# Cansat2019_3279_Container_v02.net
KiCad netlist of a schematic drawn in EAGLE
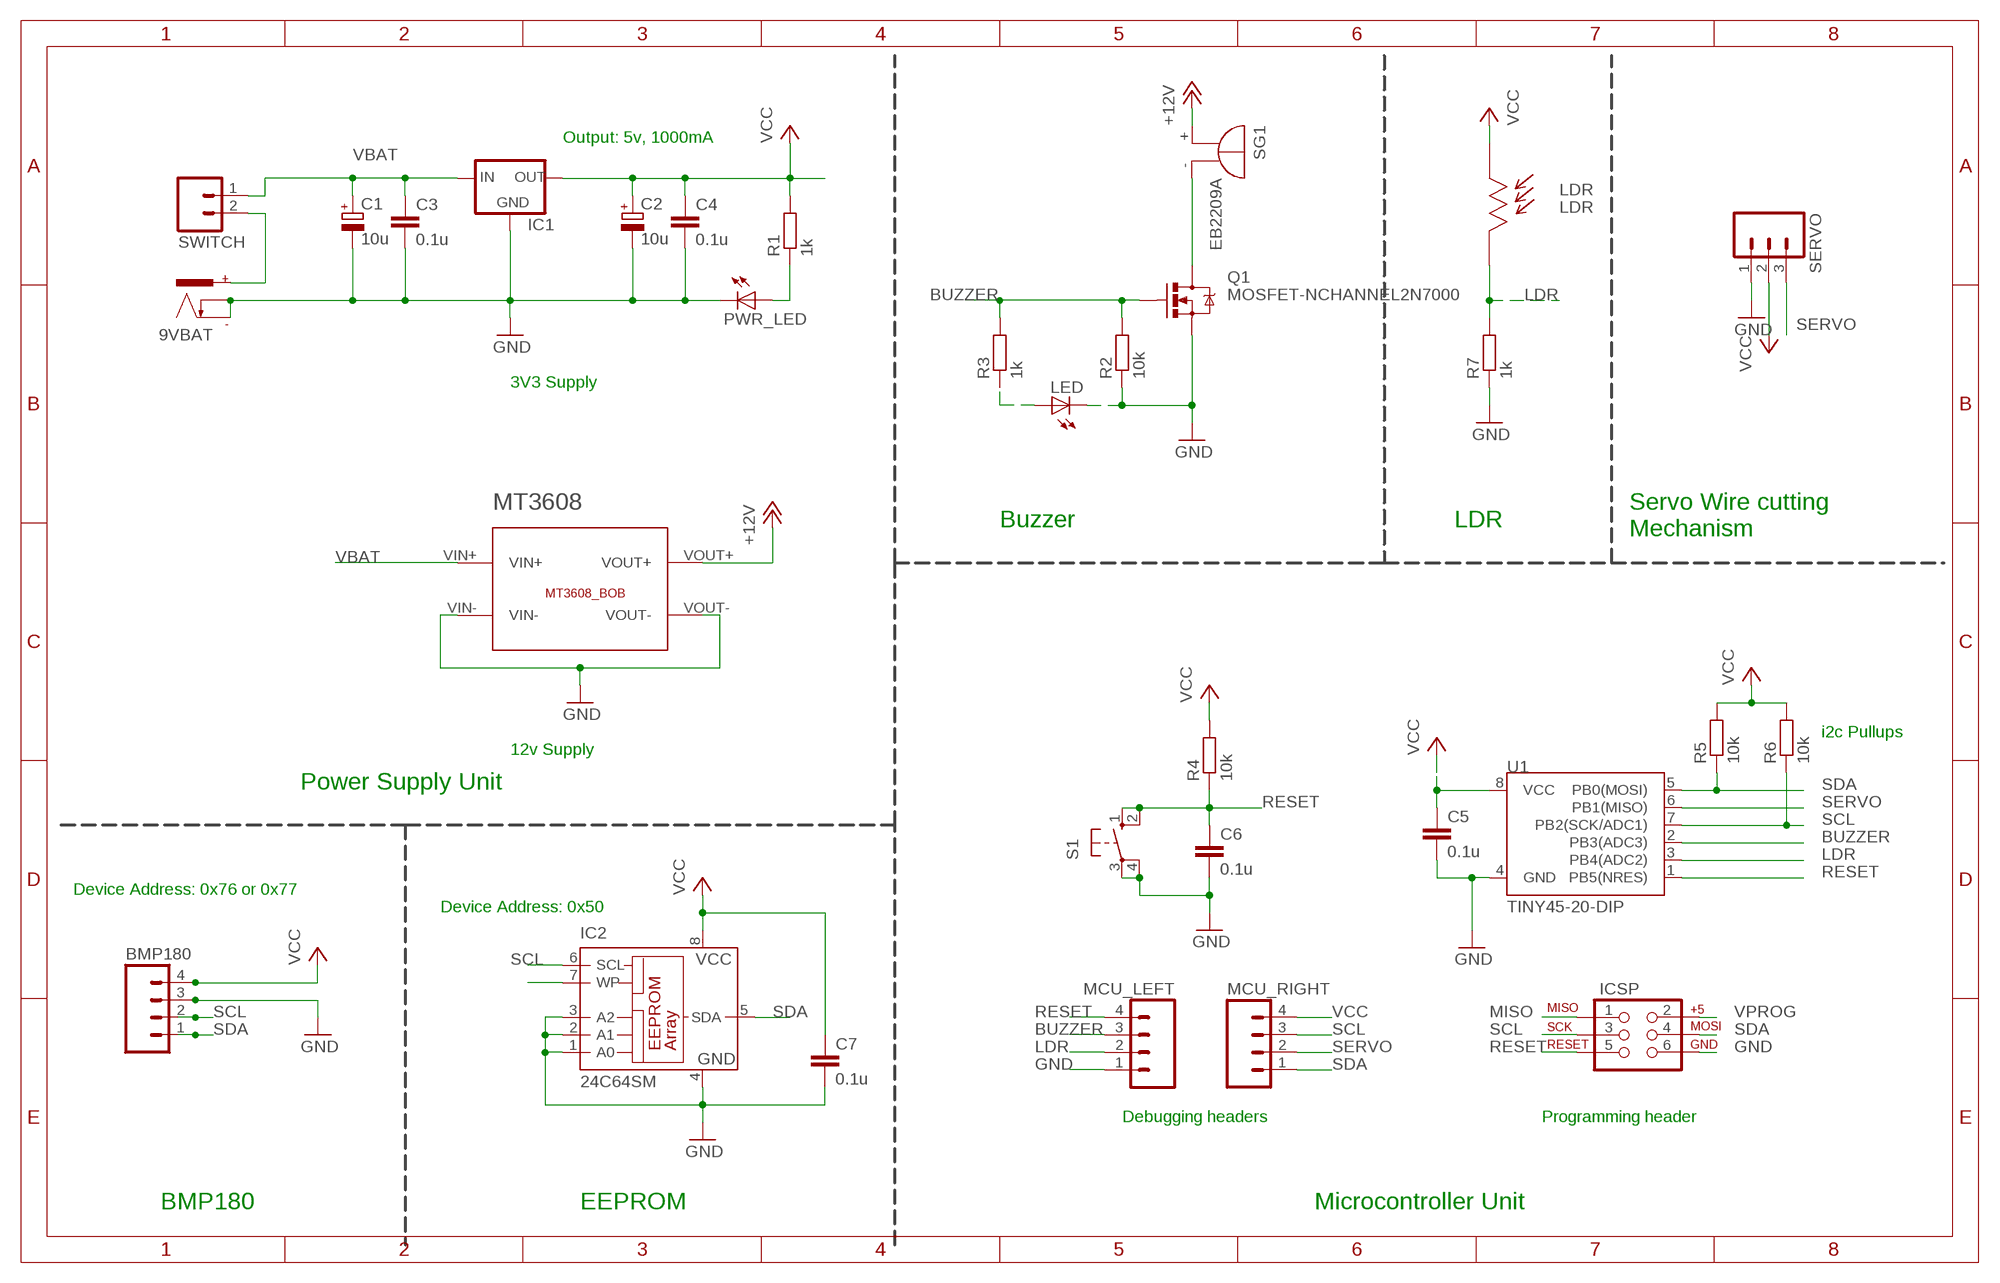
[diagram p0: schematic, sheet 1]

(export (version "E")
  (design (tool "Eeschema 10.0.6"))
  (components
    (comp (ref "9VBAT")
      (value "POWER_CON")
      (footprint "eagle-import:NEB21R")
      (libsource (lib "eagle-import") (part "POWER_CON"))
    )
    (comp (ref "BMP180")
      (value "M04")
      (footprint "eagle-import:04P")
      (libsource (lib "eagle-import") (part "M04"))
    )
    (comp (ref "C1")
      (value "10u")
      (footprint "eagle-import:E2,5-6")
      (libsource (lib "eagle-import") (part "CPOL-EUE2.5-6"))
    )
    (comp (ref "C2")
      (value "10u")
      (footprint "eagle-import:E2,5-6")
      (libsource (lib "eagle-import") (part "CPOL-EUE2.5-6"))
    )
    (comp (ref "C3")
      (value "0.1u")
      (footprint "eagle-import:C025-025X050")
      (libsource (lib "eagle-import") (part "C-EU025-025X050"))
    )
    (comp (ref "C4")
      (value "0.1u")
      (footprint "eagle-import:C025-025X050")
      (libsource (lib "eagle-import") (part "C-EU025-025X050"))
    )
    (comp (ref "C5")
      (value "0.1u")
      (footprint "eagle-import:C025-025X050")
      (libsource (lib "eagle-import") (part "C-EU025-025X050"))
    )
    (comp (ref "C6")
      (value "0.1u")
      (footprint "eagle-import:C025-025X050")
      (libsource (lib "eagle-import") (part "C-EU025-025X050"))
    )
    (comp (ref "C7")
      (value "0.1u")
      (footprint "eagle-import:C025-025X050")
      (libsource (lib "eagle-import") (part "C-EU025-025X050"))
    )
    (comp (ref "IC1")
      (value "V_REG_78XX-TO-220")
      (footprint "eagle-import:TO-220-ALT")
      (libsource (lib "eagle-import") (part "V_REG_78XX-TO-220"))
    )
    (comp (ref "IC2")
      (value "24C64SM")
      (footprint "eagle-import:SO-08M")
      (fields (field (name "MF") "RAMTRON INTERNATIONAL CORP") (field (name "MPN") "FM24C64-S"))
      (libsource (lib "eagle-import") (part "24SMC64"))
    )
    (comp (ref "ICSP")
      (value "AVR_SPI_PRG_6NS")
      (footprint "eagle-import:2X3-NS")
      (libsource (lib "eagle-import") (part "AVR_SPI_PRG_6NS"))
    )
    (comp (ref "LDR")
      (value "LDR")
      (footprint "eagle-import:LDR-5MM")
      (libsource (lib "eagle-import") (part "LDR"))
    )
    (comp (ref "LED")
      (value "LED3MM")
      (footprint "eagle-import:LED3MM")
      (libsource (lib "eagle-import") (part "LED3MM"))
    )
    (comp (ref "MCU_LEFT")
      (value "M04")
      (footprint "eagle-import:04P")
      (libsource (lib "eagle-import") (part "M04"))
    )
    (comp (ref "MCU_RIGHT")
      (value "M04")
      (footprint "eagle-import:04P")
      (libsource (lib "eagle-import") (part "M04"))
    )
    (comp (ref "MT3608")
      (value "MT3608_BOB")
      (footprint "eagle-import:MT3608_BOB")
      (libsource (lib "eagle-import") (part "MT3608_BOB"))
    )
    (comp (ref "PWR_LED")
      (value "LED3MM")
      (footprint "eagle-import:LED3MM")
      (libsource (lib "eagle-import") (part "LED3MM"))
    )
    (comp (ref "Q1")
      (value "MOSFET-NCHANNEL2N7000")
      (footprint "eagle-import:TO-92")
      (libsource (lib "eagle-import") (part "MOSFET-NCHANNEL2N7000"))
    )
    (comp (ref "R1")
      (value "1k")
      (footprint "eagle-import:0204_7")
      (libsource (lib "eagle-import") (part "R-EU_0204/7"))
    )
    (comp (ref "R2")
      (value "10k")
      (footprint "eagle-import:0204_7")
      (libsource (lib "eagle-import") (part "R-EU_0204/7"))
    )
    (comp (ref "R3")
      (value "1k")
      (footprint "eagle-import:0204_7")
      (libsource (lib "eagle-import") (part "R-EU_0204/7"))
    )
    (comp (ref "R4")
      (value "10k")
      (footprint "eagle-import:0204_7")
      (libsource (lib "eagle-import") (part "R-EU_0204/7"))
    )
    (comp (ref "R5")
      (value "10k")
      (footprint "eagle-import:0204_7")
      (libsource (lib "eagle-import") (part "R-EU_0204/7"))
    )
    (comp (ref "R6")
      (value "10k")
      (footprint "eagle-import:0204_7")
      (libsource (lib "eagle-import") (part "R-EU_0204/7"))
    )
    (comp (ref "R7")
      (value "1k")
      (footprint "eagle-import:0204_7")
      (libsource (lib "eagle-import") (part "R-EU_0204/7"))
    )
    (comp (ref "S1")
      (value "PUSH-BUTTON-6MM")
      (footprint "eagle-import:B3F-10XX")
      (libsource (lib "eagle-import") (part "PUSH-BUTTON-6MM"))
    )
    (comp (ref "SERVO")
      (value "M03")
      (footprint "eagle-import:03P")
      (libsource (lib "eagle-import") (part "M03"))
    )
    (comp (ref "SG1")
      (value "EB2209A")
      (footprint "eagle-import:EB2209A")
      (libsource (lib "eagle-import") (part "EB2209A"))
    )
    (comp (ref "SWITCH")
      (value "M02")
      (footprint "eagle-import:02P")
      (libsource (lib "eagle-import") (part "M02"))
    )
    (comp (ref "U1")
      (value "TINY45-20-DIP")
      (footprint "eagle-import:DIP08")
      (libsource (lib "eagle-import") (part "ATTINY45TINY45-20-DIP"))
    )
  )
  (nets
    (net (code "1") (name "+12V") (class "Default")
      (node (ref "MT3608") (pin "VOUT+") (pinfunction "VOUT+_VOUT+") (pintype "bidirectional"))
      (node (ref "SG1") (pin "+") (pinfunction "+_+") (pintype "passive"))
    )
    (net (code "2") (name "/BUZZER") (class "Default")
      (node (ref "MCU_LEFT") (pin "3") (pinfunction "3_3") (pintype "passive"))
      (node (ref "Q1") (pin "2") (pinfunction "G_2") (pintype "passive"))
      (node (ref "R2") (pin "2") (pinfunction "2_2") (pintype "passive"))
      (node (ref "R3") (pin "2") (pinfunction "2_2") (pintype "passive"))
      (node (ref "U1") (pin "2") (pinfunction "PB3(ADC3)_2") (pintype "bidirectional"))
    )
    (net (code "3") (name "/LDR") (class "Default")
      (node (ref "LDR") (pin "P$2") (pinfunction "P$2_P$2") (pintype "bidirectional"))
      (node (ref "MCU_LEFT") (pin "2") (pinfunction "2_2") (pintype "passive"))
      (node (ref "R7") (pin "2") (pinfunction "2_2") (pintype "passive"))
      (node (ref "U1") (pin "3") (pinfunction "PB4(ADC2)_3") (pintype "bidirectional"))
    )
    (net (code "4") (name "/MISO") (class "Default")
      (node (ref "ICSP") (pin "1") (pinfunction "1_1") (pintype "passive"))
    )
    (net (code "5") (name "/RESET") (class "Default")
      (node (ref "C6") (pin "1") (pinfunction "1_1") (pintype "passive"))
      (node (ref "ICSP") (pin "5") (pinfunction "5_5") (pintype "passive"))
      (node (ref "MCU_LEFT") (pin "4") (pinfunction "4_4") (pintype "passive"))
      (node (ref "R4") (pin "1") (pinfunction "1_1") (pintype "passive"))
      (node (ref "S1") (pin "1") (pinfunction "S_1") (pintype "passive"))
      (node (ref "S1") (pin "2") (pinfunction "S1_2") (pintype "passive"))
      (node (ref "U1") (pin "1") (pinfunction "PB5(NRES)_1") (pintype "bidirectional"))
    )
    (net (code "6") (name "/SCL") (class "Default")
      (node (ref "BMP180") (pin "2") (pinfunction "2_2") (pintype "passive"))
      (node (ref "IC2") (pin "6") (pinfunction "SCL_6") (pintype "input"))
      (node (ref "ICSP") (pin "3") (pinfunction "3_3") (pintype "passive"))
      (node (ref "MCU_RIGHT") (pin "3") (pinfunction "3_3") (pintype "passive"))
      (node (ref "R6") (pin "1") (pinfunction "1_1") (pintype "passive"))
      (node (ref "U1") (pin "7") (pinfunction "PB2(SCK/ADC1)_7") (pintype "bidirectional"))
    )
    (net (code "7") (name "/SDA") (class "Default")
      (node (ref "BMP180") (pin "1") (pinfunction "1_1") (pintype "passive"))
      (node (ref "IC2") (pin "5") (pinfunction "SDA_5") (pintype "bidirectional"))
      (node (ref "ICSP") (pin "4") (pinfunction "4_4") (pintype "passive"))
      (node (ref "MCU_RIGHT") (pin "1") (pinfunction "1_1") (pintype "passive"))
      (node (ref "R5") (pin "1") (pinfunction "1_1") (pintype "passive"))
      (node (ref "U1") (pin "5") (pinfunction "PB0(MOSI)_5") (pintype "bidirectional"))
    )
    (net (code "8") (name "/SERVO") (class "Default")
      (node (ref "MCU_RIGHT") (pin "2") (pinfunction "2_2") (pintype "passive"))
      (node (ref "SERVO") (pin "3") (pinfunction "3_3") (pintype "passive"))
      (node (ref "U1") (pin "6") (pinfunction "PB1(MISO)_6") (pintype "bidirectional"))
    )
    (net (code "9") (name "/VBAT") (class "Default")
      (node (ref "C1") (pin "+") (pinfunction "+_+") (pintype "passive"))
      (node (ref "C3") (pin "1") (pinfunction "1_1") (pintype "passive"))
      (node (ref "IC1") (pin "IN") (pinfunction "IN_IN") (pintype "input"))
      (node (ref "MT3608") (pin "VIN+") (pinfunction "VIN+_VIN+") (pintype "bidirectional"))
      (node (ref "SWITCH") (pin "1") (pinfunction "1_1") (pintype "passive"))
    )
    (net (code "10") (name "/VPROG") (class "Default")
      (node (ref "ICSP") (pin "2") (pinfunction "2_2") (pintype "passive"))
    )
    (net (code "11") (name "GND") (class "Default")
      (node (ref "9VBAT") (pin "-") (pinfunction "-_-") (pintype "passive"))
      (node (ref "9VBAT") (pin "C") (pinfunction "C_C") (pintype "passive"))
      (node (ref "BMP180") (pin "3") (pinfunction "3_3") (pintype "passive"))
      (node (ref "C1") (pin "-") (pinfunction "-_-") (pintype "passive"))
      (node (ref "C2") (pin "-") (pinfunction "-_-") (pintype "passive"))
      (node (ref "C3") (pin "2") (pinfunction "2_2") (pintype "passive"))
      (node (ref "C4") (pin "2") (pinfunction "2_2") (pintype "passive"))
      (node (ref "C5") (pin "2") (pinfunction "2_2") (pintype "passive"))
      (node (ref "C6") (pin "2") (pinfunction "2_2") (pintype "passive"))
      (node (ref "C7") (pin "2") (pinfunction "2_2") (pintype "passive"))
      (node (ref "IC1") (pin "GND") (pinfunction "GND_GND") (pintype "input"))
      (node (ref "IC2") (pin "1") (pinfunction "A0_1") (pintype "input"))
      (node (ref "IC2") (pin "2") (pinfunction "A1_2") (pintype "input"))
      (node (ref "IC2") (pin "3") (pinfunction "A2_3") (pintype "input"))
      (node (ref "IC2") (pin "4") (pinfunction "GND_4") (pintype "power_in"))
      (node (ref "ICSP") (pin "6") (pinfunction "6_6") (pintype "passive"))
      (node (ref "LED") (pin "K") (pinfunction "C_K") (pintype "passive"))
      (node (ref "MCU_LEFT") (pin "1") (pinfunction "1_1") (pintype "passive"))
      (node (ref "MT3608") (pin "VIN-") (pinfunction "VIN-_VIN-") (pintype "bidirectional"))
      (node (ref "MT3608") (pin "VOUT-") (pinfunction "VOUT-_VOUT-") (pintype "bidirectional"))
      (node (ref "PWR_LED") (pin "K") (pinfunction "C_K") (pintype "passive"))
      (node (ref "Q1") (pin "1") (pinfunction "S_1") (pintype "passive"))
      (node (ref "R2") (pin "1") (pinfunction "1_1") (pintype "passive"))
      (node (ref "R7") (pin "1") (pinfunction "1_1") (pintype "passive"))
      (node (ref "S1") (pin "3") (pinfunction "P_3") (pintype "passive"))
      (node (ref "S1") (pin "4") (pinfunction "P1_4") (pintype "passive"))
      (node (ref "SERVO") (pin "1") (pinfunction "1_1") (pintype "passive"))
      (node (ref "U1") (pin "4") (pinfunction "GND_4") (pintype "bidirectional"))
    )
    (net (code "12") (name "Net-(9VBAT-Pad+)") (class "Default")
      (node (ref "9VBAT") (pin "+") (pinfunction "+_+") (pintype "passive"))
      (node (ref "SWITCH") (pin "2") (pinfunction "2_2") (pintype "passive"))
    )
    (net (code "13") (name "Net-(LED-PadA)") (class "Default")
      (node (ref "LED") (pin "A") (pinfunction "A_A") (pintype "passive"))
      (node (ref "R3") (pin "1") (pinfunction "1_1") (pintype "passive"))
    )
    (net (code "14") (name "Net-(PWR_LED-PadA)") (class "Default")
      (node (ref "PWR_LED") (pin "A") (pinfunction "A_A") (pintype "passive"))
      (node (ref "R1") (pin "1") (pinfunction "1_1") (pintype "passive"))
    )
    (net (code "15") (name "Net-(Q1-D)") (class "Default")
      (node (ref "Q1") (pin "3") (pinfunction "D_3") (pintype "passive"))
      (node (ref "SG1") (pin "-") (pinfunction "-_-") (pintype "passive"))
    )
    (net (code "16") (name "VCC") (class "Default")
      (node (ref "BMP180") (pin "4") (pinfunction "4_4") (pintype "passive"))
      (node (ref "C2") (pin "+") (pinfunction "+_+") (pintype "passive"))
      (node (ref "C4") (pin "1") (pinfunction "1_1") (pintype "passive"))
      (node (ref "C5") (pin "1") (pinfunction "1_1") (pintype "passive"))
      (node (ref "C7") (pin "1") (pinfunction "1_1") (pintype "passive"))
      (node (ref "IC1") (pin "OUT") (pinfunction "OUT_OUT") (pintype "output"))
      (node (ref "IC2") (pin "8") (pinfunction "VCC_8") (pintype "power_in"))
      (node (ref "LDR") (pin "P$1") (pinfunction "P$1_P$1") (pintype "bidirectional"))
      (node (ref "MCU_RIGHT") (pin "4") (pinfunction "4_4") (pintype "passive"))
      (node (ref "R1") (pin "2") (pinfunction "2_2") (pintype "passive"))
      (node (ref "R4") (pin "2") (pinfunction "2_2") (pintype "passive"))
      (node (ref "R5") (pin "2") (pinfunction "2_2") (pintype "passive"))
      (node (ref "R6") (pin "2") (pinfunction "2_2") (pintype "passive"))
      (node (ref "SERVO") (pin "2") (pinfunction "2_2") (pintype "passive"))
      (node (ref "U1") (pin "8") (pinfunction "VCC_8") (pintype "bidirectional"))
    )
    (net (code "17") (name "unconnected-(IC2-WP-Pad7)") (class "Default")
      (node (ref "IC2") (pin "7") (pinfunction "WP_7") (pintype "input"))
    )
  )
)
